# Line_Camera_Rev_A.net
KiCad netlist of a schematic drawn in EAGLE
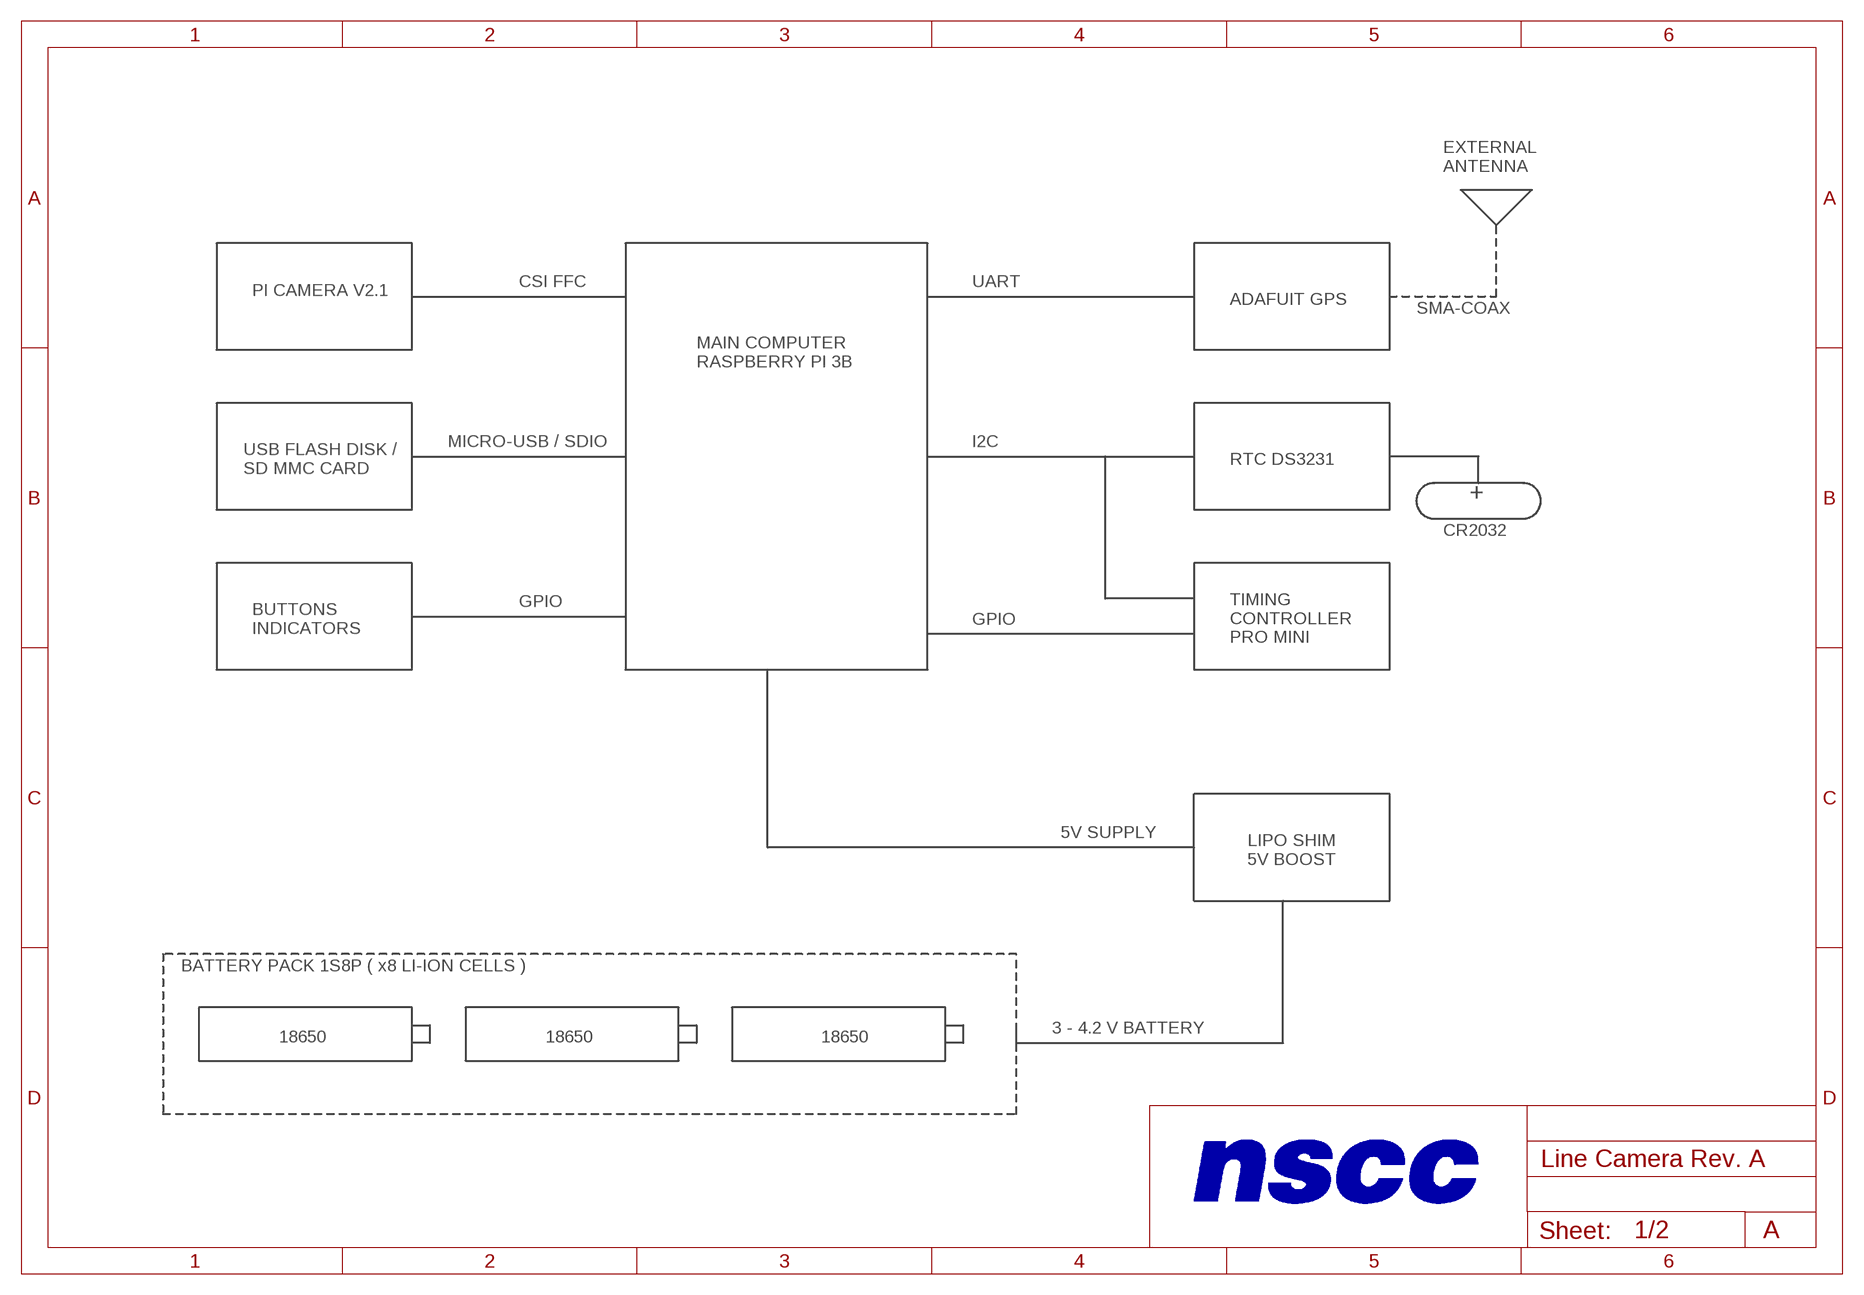
[diagram p0: schematic, sheet 1]
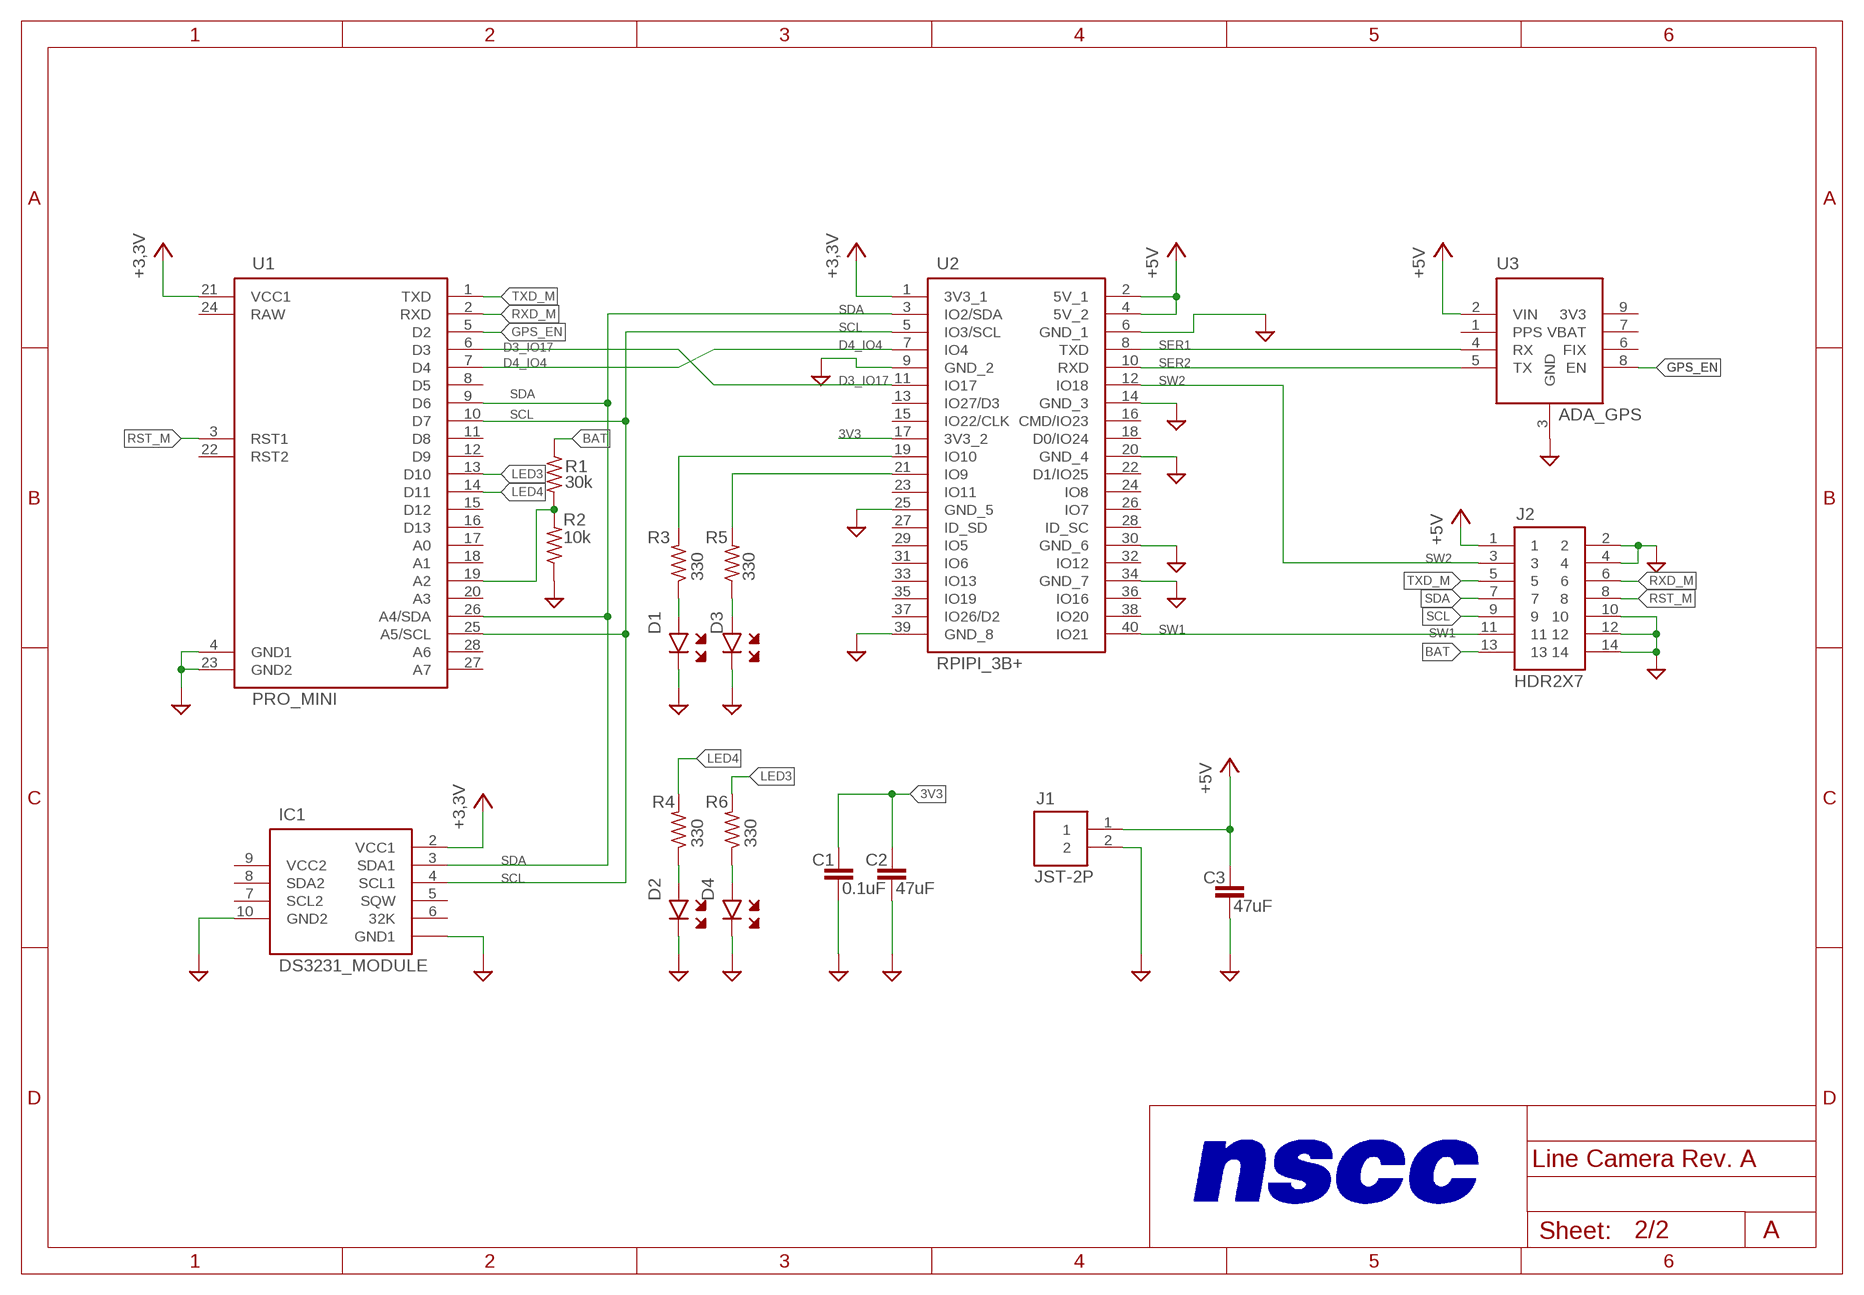
[diagram p1: schematic, sheet 2]

(export (version "E")
  (design (tool "Eeschema 10.0.6"))
  (components
    (comp (ref "C1")
      (value "0.1uF")
      (footprint "eagle-import:CAPPRD254W65D300H300B")
      (libsource (lib "eagle-import") (part "CAP_THCAP-TH-2MM"))
    )
    (comp (ref "C2")
      (value "47uF")
      (footprint "eagle-import:CAPPRD508W65D1000H1100B")
      (libsource (lib "eagle-import") (part "CAP_THCAP-ELECTRO-5.08"))
    )
    (comp (ref "C3")
      (value "47uF")
      (footprint "eagle-import:CAPPRD508W65D1000H1100B")
      (libsource (lib "eagle-import") (part "CAP_THCAP-ELECTRO-5.08"))
    )
    (comp (ref "D1")
      (value "LED_THLED-2.54")
      (footprint "eagle-import:LEDRD254W60D565H860B")
      (libsource (lib "eagle-import") (part "LED_THLED-2.54"))
    )
    (comp (ref "D2")
      (value "LED_THLED-2.54")
      (footprint "eagle-import:LEDRD254W60D565H860B")
      (libsource (lib "eagle-import") (part "LED_THLED-2.54"))
    )
    (comp (ref "D3")
      (value "LED_THLED-2.54")
      (footprint "eagle-import:LEDRD254W60D565H860B")
      (libsource (lib "eagle-import") (part "LED_THLED-2.54"))
    )
    (comp (ref "D4")
      (value "LED_THLED-2.54")
      (footprint "eagle-import:LEDRD254W60D565H860B")
      (libsource (lib "eagle-import") (part "LED_THLED-2.54"))
    )
    (comp (ref "IC1")
      (value "DS3231_MODULE")
      (footprint "eagle-import:DS3231_MODULE")
      (libsource (lib "eagle-import") (part "DS3231_MODULE"))
    )
    (comp (ref "J1")
      (value "JST-2P")
      (footprint "eagle-import:HDR1X2")
      (libsource (lib "eagle-import") (part "HDR1X22P2.54MM"))
    )
    (comp (ref "J2")
      (value "HDR2X7")
      (footprint "eagle-import:HDR2X7")
      (libsource (lib "eagle-import") (part "HDR2X7HDR2X7"))
    )
    (comp (ref "R1")
      (value "30k")
      (footprint "eagle-import:RESAD1176W63L850D250B")
      (libsource (lib "eagle-import") (part "RES_THRES-D8.5"))
    )
    (comp (ref "R2")
      (value "10k")
      (footprint "eagle-import:RESAD1176W63L850D250B")
      (libsource (lib "eagle-import") (part "RES_THRES-D8.5"))
    )
    (comp (ref "R3")
      (value "330")
      (footprint "eagle-import:RESAD1176W63L850D250B")
      (libsource (lib "eagle-import") (part "RES_THRES-D8.5"))
    )
    (comp (ref "R4")
      (value "330")
      (footprint "eagle-import:RESAD1176W63L850D250B")
      (libsource (lib "eagle-import") (part "RES_THRES-D8.5"))
    )
    (comp (ref "R5")
      (value "330")
      (footprint "eagle-import:RESAD1176W63L850D250B")
      (libsource (lib "eagle-import") (part "RES_THRES-D8.5"))
    )
    (comp (ref "R6")
      (value "330")
      (footprint "eagle-import:RESAD1176W63L850D250B")
      (libsource (lib "eagle-import") (part "RES_THRES-D8.5"))
    )
    (comp (ref "U1")
      (value "PRO_MINI")
      (footprint "eagle-import:PRO_MINI")
      (libsource (lib "eagle-import") (part "PRO_MINI"))
    )
    (comp (ref "U2")
      (value "RPIPI_3B+")
      (footprint "eagle-import:PI_3B")
      (libsource (lib "eagle-import") (part "RPIPI_3B+"))
    )
    (comp (ref "U3")
      (value "ADA_GPS")
      (footprint "eagle-import:ADA_ULTIMATE_GPS")
      (libsource (lib "eagle-import") (part "ADA_ULTIMATE_GPS9P_BREAKOUT"))
    )
  )
  (nets
    (net (code "1") (name "+3,3V") (class "Default")
      (node (ref "IC1") (pin "2") (pinfunction "VCC1_2") (pintype "bidirectional"))
      (node (ref "U1") (pin "21") (pinfunction "VCC1_21") (pintype "bidirectional"))
      (node (ref "U2") (pin "1") (pinfunction "3V3_1_1") (pintype "bidirectional"))
    )
    (net (code "2") (name "+5V") (class "Default")
      (node (ref "C3") (pin "1") (pinfunction "1_1") (pintype "passive"))
      (node (ref "J1") (pin "1") (pinfunction "1_1") (pintype "bidirectional"))
      (node (ref "J2") (pin "1") (pinfunction "1_1") (pintype "bidirectional"))
      (node (ref "U2") (pin "2") (pinfunction "5V_1_2") (pintype "bidirectional"))
      (node (ref "U2") (pin "4") (pinfunction "5V_2_4") (pintype "bidirectional"))
      (node (ref "U3") (pin "2") (pinfunction "VIN_2") (pintype "bidirectional"))
    )
    (net (code "3") (name "3V3") (class "Default")
      (node (ref "C1") (pin "1") (pinfunction "1_1") (pintype "passive"))
      (node (ref "C2") (pin "1") (pinfunction "1_1") (pintype "passive"))
      (node (ref "U2") (pin "17") (pinfunction "3V3_2_17") (pintype "bidirectional"))
    )
    (net (code "4") (name "BAT") (class "Default")
      (node (ref "J2") (pin "13") (pinfunction "13_13") (pintype "bidirectional"))
      (node (ref "R1") (pin "1") (pinfunction "1_1") (pintype "passive"))
    )
    (net (code "5") (name "D3_IO17") (class "Default")
      (node (ref "U1") (pin "6") (pinfunction "D3_6") (pintype "bidirectional"))
      (node (ref "U2") (pin "11") (pinfunction "IO17_11") (pintype "bidirectional"))
    )
    (net (code "6") (name "D4_IO4") (class "Default")
      (node (ref "U1") (pin "7") (pinfunction "D4_7") (pintype "bidirectional"))
      (node (ref "U2") (pin "7") (pinfunction "IO4_7") (pintype "bidirectional"))
    )
    (net (code "7") (name "GND") (class "Default")
      (node (ref "C1") (pin "2") (pinfunction "2_2") (pintype "passive"))
      (node (ref "C2") (pin "2") (pinfunction "2_2") (pintype "passive"))
      (node (ref "C3") (pin "2") (pinfunction "2_2") (pintype "passive"))
      (node (ref "D1") (pin "2") (pinfunction "P$2_2") (pintype "bidirectional"))
      (node (ref "D2") (pin "2") (pinfunction "P$2_2") (pintype "bidirectional"))
      (node (ref "D3") (pin "2") (pinfunction "P$2_2") (pintype "bidirectional"))
      (node (ref "D4") (pin "2") (pinfunction "P$2_2") (pintype "bidirectional"))
      (node (ref "IC1") (pin "1") (pinfunction "GND1_1") (pintype "bidirectional"))
      (node (ref "IC1") (pin "10") (pinfunction "GND2_10") (pintype "bidirectional"))
      (node (ref "J1") (pin "2") (pinfunction "2_2") (pintype "bidirectional"))
      (node (ref "J2") (pin "10") (pinfunction "10_10") (pintype "bidirectional"))
      (node (ref "J2") (pin "12") (pinfunction "12_12") (pintype "bidirectional"))
      (node (ref "J2") (pin "14") (pinfunction "14_14") (pintype "bidirectional"))
      (node (ref "J2") (pin "2") (pinfunction "2_2") (pintype "bidirectional"))
      (node (ref "J2") (pin "4") (pinfunction "4_4") (pintype "bidirectional"))
      (node (ref "R2") (pin "1") (pinfunction "1_1") (pintype "passive"))
      (node (ref "U1") (pin "23") (pinfunction "GND2_23") (pintype "bidirectional"))
      (node (ref "U1") (pin "4") (pinfunction "GND1_4") (pintype "bidirectional"))
      (node (ref "U2") (pin "14") (pinfunction "GND_3_14") (pintype "bidirectional"))
      (node (ref "U2") (pin "20") (pinfunction "GND_4_20") (pintype "bidirectional"))
      (node (ref "U2") (pin "25") (pinfunction "GND_5_25") (pintype "bidirectional"))
      (node (ref "U2") (pin "30") (pinfunction "GND_6_30") (pintype "bidirectional"))
      (node (ref "U2") (pin "34") (pinfunction "GND_7_34") (pintype "bidirectional"))
      (node (ref "U2") (pin "39") (pinfunction "GND_8_39") (pintype "bidirectional"))
      (node (ref "U2") (pin "6") (pinfunction "GND_1_6") (pintype "bidirectional"))
      (node (ref "U2") (pin "9") (pinfunction "GND_2_9") (pintype "bidirectional"))
      (node (ref "U3") (pin "3") (pinfunction "GND_3") (pintype "bidirectional"))
    )
    (net (code "8") (name "GPS_EN") (class "Default")
      (node (ref "U1") (pin "5") (pinfunction "D2_5") (pintype "bidirectional"))
      (node (ref "U3") (pin "8") (pinfunction "EN_8") (pintype "bidirectional"))
    )
    (net (code "9") (name "LED3") (class "Default")
      (node (ref "R6") (pin "2") (pinfunction "2_2") (pintype "passive"))
      (node (ref "U1") (pin "13") (pinfunction "D10_13") (pintype "bidirectional"))
    )
    (net (code "10") (name "LED4") (class "Default")
      (node (ref "R4") (pin "2") (pinfunction "2_2") (pintype "passive"))
      (node (ref "U1") (pin "14") (pinfunction "D11_14") (pintype "bidirectional"))
    )
    (net (code "11") (name "Net-(D1-P$1)") (class "Default")
      (node (ref "D1") (pin "1") (pinfunction "P$1_1") (pintype "bidirectional"))
      (node (ref "R3") (pin "1") (pinfunction "1_1") (pintype "passive"))
    )
    (net (code "12") (name "Net-(D2-P$1)") (class "Default")
      (node (ref "D2") (pin "1") (pinfunction "P$1_1") (pintype "bidirectional"))
      (node (ref "R4") (pin "1") (pinfunction "1_1") (pintype "passive"))
    )
    (net (code "13") (name "Net-(D3-P$1)") (class "Default")
      (node (ref "D3") (pin "1") (pinfunction "P$1_1") (pintype "bidirectional"))
      (node (ref "R5") (pin "1") (pinfunction "1_1") (pintype "passive"))
    )
    (net (code "14") (name "Net-(D4-P$1)") (class "Default")
      (node (ref "D4") (pin "1") (pinfunction "P$1_1") (pintype "bidirectional"))
      (node (ref "R6") (pin "1") (pinfunction "1_1") (pintype "passive"))
    )
    (net (code "15") (name "Net-(U1-A2)") (class "Default")
      (node (ref "R1") (pin "2") (pinfunction "2_2") (pintype "passive"))
      (node (ref "R2") (pin "2") (pinfunction "2_2") (pintype "passive"))
      (node (ref "U1") (pin "19") (pinfunction "A2_19") (pintype "bidirectional"))
    )
    (net (code "16") (name "Net-(U2-IO9)") (class "Default")
      (node (ref "R5") (pin "2") (pinfunction "2_2") (pintype "passive"))
      (node (ref "U2") (pin "21") (pinfunction "IO9_21") (pintype "bidirectional"))
    )
    (net (code "17") (name "Net-(U2-IO10)") (class "Default")
      (node (ref "R3") (pin "2") (pinfunction "2_2") (pintype "passive"))
      (node (ref "U2") (pin "19") (pinfunction "IO10_19") (pintype "bidirectional"))
    )
    (net (code "18") (name "RST_M") (class "Default")
      (node (ref "J2") (pin "8") (pinfunction "8_8") (pintype "bidirectional"))
      (node (ref "U1") (pin "3") (pinfunction "RST1_3") (pintype "bidirectional"))
    )
    (net (code "19") (name "RXD_M") (class "Default")
      (node (ref "J2") (pin "6") (pinfunction "6_6") (pintype "bidirectional"))
      (node (ref "U1") (pin "2") (pinfunction "RXD_2") (pintype "bidirectional"))
    )
    (net (code "20") (name "SCL") (class "Default")
      (node (ref "IC1") (pin "4") (pinfunction "SCL1_4") (pintype "bidirectional"))
      (node (ref "J2") (pin "9") (pinfunction "9_9") (pintype "bidirectional"))
      (node (ref "U1") (pin "10") (pinfunction "D7_10") (pintype "bidirectional"))
      (node (ref "U1") (pin "25") (pinfunction "A5/SCL_25") (pintype "bidirectional"))
      (node (ref "U2") (pin "5") (pinfunction "IO3/SCL_5") (pintype "bidirectional"))
    )
    (net (code "21") (name "SDA") (class "Default")
      (node (ref "IC1") (pin "3") (pinfunction "SDA1_3") (pintype "bidirectional"))
      (node (ref "J2") (pin "7") (pinfunction "7_7") (pintype "bidirectional"))
      (node (ref "U1") (pin "26") (pinfunction "A4/SDA_26") (pintype "bidirectional"))
      (node (ref "U1") (pin "9") (pinfunction "D6_9") (pintype "bidirectional"))
      (node (ref "U2") (pin "3") (pinfunction "IO2/SDA_3") (pintype "bidirectional"))
    )
    (net (code "22") (name "SER1") (class "Default")
      (node (ref "U2") (pin "8") (pinfunction "TXD_8") (pintype "bidirectional"))
      (node (ref "U3") (pin "4") (pinfunction "RX_4") (pintype "bidirectional"))
    )
    (net (code "23") (name "SER2") (class "Default")
      (node (ref "U2") (pin "10") (pinfunction "RXD_10") (pintype "bidirectional"))
      (node (ref "U3") (pin "5") (pinfunction "TX_5") (pintype "bidirectional"))
    )
    (net (code "24") (name "SW1") (class "Default")
      (node (ref "J2") (pin "11") (pinfunction "11_11") (pintype "bidirectional"))
      (node (ref "U2") (pin "40") (pinfunction "IO21_40") (pintype "bidirectional"))
    )
    (net (code "25") (name "SW2") (class "Default")
      (node (ref "J2") (pin "3") (pinfunction "3_3") (pintype "bidirectional"))
      (node (ref "U2") (pin "12") (pinfunction "IO18_12") (pintype "bidirectional"))
    )
    (net (code "26") (name "TXD_M") (class "Default")
      (node (ref "J2") (pin "5") (pinfunction "5_5") (pintype "bidirectional"))
      (node (ref "U1") (pin "1") (pinfunction "TXD_1") (pintype "bidirectional"))
    )
    (net (code "27") (name "unconnected-(IC1-32K-Pad6)") (class "Default")
      (node (ref "IC1") (pin "6") (pinfunction "32K_6") (pintype "bidirectional"))
    )
    (net (code "28") (name "unconnected-(IC1-SCL2-Pad7)") (class "Default")
      (node (ref "IC1") (pin "7") (pinfunction "SCL2_7") (pintype "bidirectional"))
    )
    (net (code "29") (name "unconnected-(IC1-SDA2-Pad8)") (class "Default")
      (node (ref "IC1") (pin "8") (pinfunction "SDA2_8") (pintype "bidirectional"))
    )
    (net (code "30") (name "unconnected-(IC1-SQW-Pad5)") (class "Default")
      (node (ref "IC1") (pin "5") (pinfunction "SQW_5") (pintype "bidirectional"))
    )
    (net (code "31") (name "unconnected-(IC1-VCC2-Pad9)") (class "Default")
      (node (ref "IC1") (pin "9") (pinfunction "VCC2_9") (pintype "bidirectional"))
    )
    (net (code "32") (name "unconnected-(U1-A0-Pad17)") (class "Default")
      (node (ref "U1") (pin "17") (pinfunction "A0_17") (pintype "bidirectional"))
    )
    (net (code "33") (name "unconnected-(U1-A1-Pad18)") (class "Default")
      (node (ref "U1") (pin "18") (pinfunction "A1_18") (pintype "bidirectional"))
    )
    (net (code "34") (name "unconnected-(U1-A3-Pad20)") (class "Default")
      (node (ref "U1") (pin "20") (pinfunction "A3_20") (pintype "bidirectional"))
    )
    (net (code "35") (name "unconnected-(U1-A6-Pad28)") (class "Default")
      (node (ref "U1") (pin "28") (pinfunction "A6_28") (pintype "bidirectional"))
    )
    (net (code "36") (name "unconnected-(U1-A7-Pad27)") (class "Default")
      (node (ref "U1") (pin "27") (pinfunction "A7_27") (pintype "bidirectional"))
    )
    (net (code "37") (name "unconnected-(U1-D5-Pad8)") (class "Default")
      (node (ref "U1") (pin "8") (pinfunction "D5_8") (pintype "bidirectional"))
    )
    (net (code "38") (name "unconnected-(U1-D8-Pad11)") (class "Default")
      (node (ref "U1") (pin "11") (pinfunction "D8_11") (pintype "bidirectional"))
    )
    (net (code "39") (name "unconnected-(U1-D9-Pad12)") (class "Default")
      (node (ref "U1") (pin "12") (pinfunction "D9_12") (pintype "bidirectional"))
    )
    (net (code "40") (name "unconnected-(U1-D12-Pad15)") (class "Default")
      (node (ref "U1") (pin "15") (pinfunction "D12_15") (pintype "bidirectional"))
    )
    (net (code "41") (name "unconnected-(U1-D13-Pad16)") (class "Default")
      (node (ref "U1") (pin "16") (pinfunction "D13_16") (pintype "bidirectional"))
    )
    (net (code "42") (name "unconnected-(U1-RAW-Pad24)") (class "Default")
      (node (ref "U1") (pin "24") (pinfunction "RAW_24") (pintype "bidirectional"))
    )
    (net (code "43") (name "unconnected-(U1-RST2-Pad22)") (class "Default")
      (node (ref "U1") (pin "22") (pinfunction "RST2_22") (pintype "bidirectional"))
    )
    (net (code "44") (name "unconnected-(U2-CMD{slash}IO23-Pad16)") (class "Default")
      (node (ref "U2") (pin "16") (pinfunction "CMD/IO23_16") (pintype "bidirectional"))
    )
    (net (code "45") (name "unconnected-(U2-D0{slash}IO24-Pad18)") (class "Default")
      (node (ref "U2") (pin "18") (pinfunction "D0/IO24_18") (pintype "bidirectional"))
    )
    (net (code "46") (name "unconnected-(U2-D1{slash}IO25-Pad22)") (class "Default")
      (node (ref "U2") (pin "22") (pinfunction "D1/IO25_22") (pintype "bidirectional"))
    )
    (net (code "47") (name "unconnected-(U2-ID_SC-Pad28)") (class "Default")
      (node (ref "U2") (pin "28") (pinfunction "ID_SC_28") (pintype "bidirectional"))
    )
    (net (code "48") (name "unconnected-(U2-ID_SD-Pad27)") (class "Default")
      (node (ref "U2") (pin "27") (pinfunction "ID_SD_27") (pintype "bidirectional"))
    )
    (net (code "49") (name "unconnected-(U2-IO5-Pad29)") (class "Default")
      (node (ref "U2") (pin "29") (pinfunction "IO5_29") (pintype "bidirectional"))
    )
    (net (code "50") (name "unconnected-(U2-IO6-Pad31)") (class "Default")
      (node (ref "U2") (pin "31") (pinfunction "IO6_31") (pintype "bidirectional"))
    )
    (net (code "51") (name "unconnected-(U2-IO7-Pad26)") (class "Default")
      (node (ref "U2") (pin "26") (pinfunction "IO7_26") (pintype "bidirectional"))
    )
    (net (code "52") (name "unconnected-(U2-IO8-Pad24)") (class "Default")
      (node (ref "U2") (pin "24") (pinfunction "IO8_24") (pintype "bidirectional"))
    )
    (net (code "53") (name "unconnected-(U2-IO11-Pad23)") (class "Default")
      (node (ref "U2") (pin "23") (pinfunction "IO11_23") (pintype "bidirectional"))
    )
    (net (code "54") (name "unconnected-(U2-IO12-Pad32)") (class "Default")
      (node (ref "U2") (pin "32") (pinfunction "IO12_32") (pintype "bidirectional"))
    )
    (net (code "55") (name "unconnected-(U2-IO13-Pad33)") (class "Default")
      (node (ref "U2") (pin "33") (pinfunction "IO13_33") (pintype "bidirectional"))
    )
    (net (code "56") (name "unconnected-(U2-IO16-Pad36)") (class "Default")
      (node (ref "U2") (pin "36") (pinfunction "IO16_36") (pintype "bidirectional"))
    )
    (net (code "57") (name "unconnected-(U2-IO19-Pad35)") (class "Default")
      (node (ref "U2") (pin "35") (pinfunction "IO19_35") (pintype "bidirectional"))
    )
    (net (code "58") (name "unconnected-(U2-IO20-Pad38)") (class "Default")
      (node (ref "U2") (pin "38") (pinfunction "IO20_38") (pintype "bidirectional"))
    )
    (net (code "59") (name "unconnected-(U2-IO22{slash}CLK-Pad15)") (class "Default")
      (node (ref "U2") (pin "15") (pinfunction "IO22/CLK_15") (pintype "bidirectional"))
    )
    (net (code "60") (name "unconnected-(U2-IO26{slash}D2-Pad37)") (class "Default")
      (node (ref "U2") (pin "37") (pinfunction "IO26/D2_37") (pintype "bidirectional"))
    )
    (net (code "61") (name "unconnected-(U2-IO27{slash}D3-Pad13)") (class "Default")
      (node (ref "U2") (pin "13") (pinfunction "IO27/D3_13") (pintype "bidirectional"))
    )
    (net (code "62") (name "unconnected-(U3-3V3-Pad9)") (class "Default")
      (node (ref "U3") (pin "9") (pinfunction "3V3_9") (pintype "bidirectional"))
    )
    (net (code "63") (name "unconnected-(U3-FIX-Pad6)") (class "Default")
      (node (ref "U3") (pin "6") (pinfunction "FIX_6") (pintype "bidirectional"))
    )
    (net (code "64") (name "unconnected-(U3-PPS-Pad1)") (class "Default")
      (node (ref "U3") (pin "1") (pinfunction "PPS_1") (pintype "bidirectional"))
    )
    (net (code "65") (name "unconnected-(U3-VBAT-Pad7)") (class "Default")
      (node (ref "U3") (pin "7") (pinfunction "VBAT_7") (pintype "bidirectional"))
    )
  )
)
